# ArtNet_LED_Strip_Controller.net
KiCad netlist of a schematic drawn in EAGLE
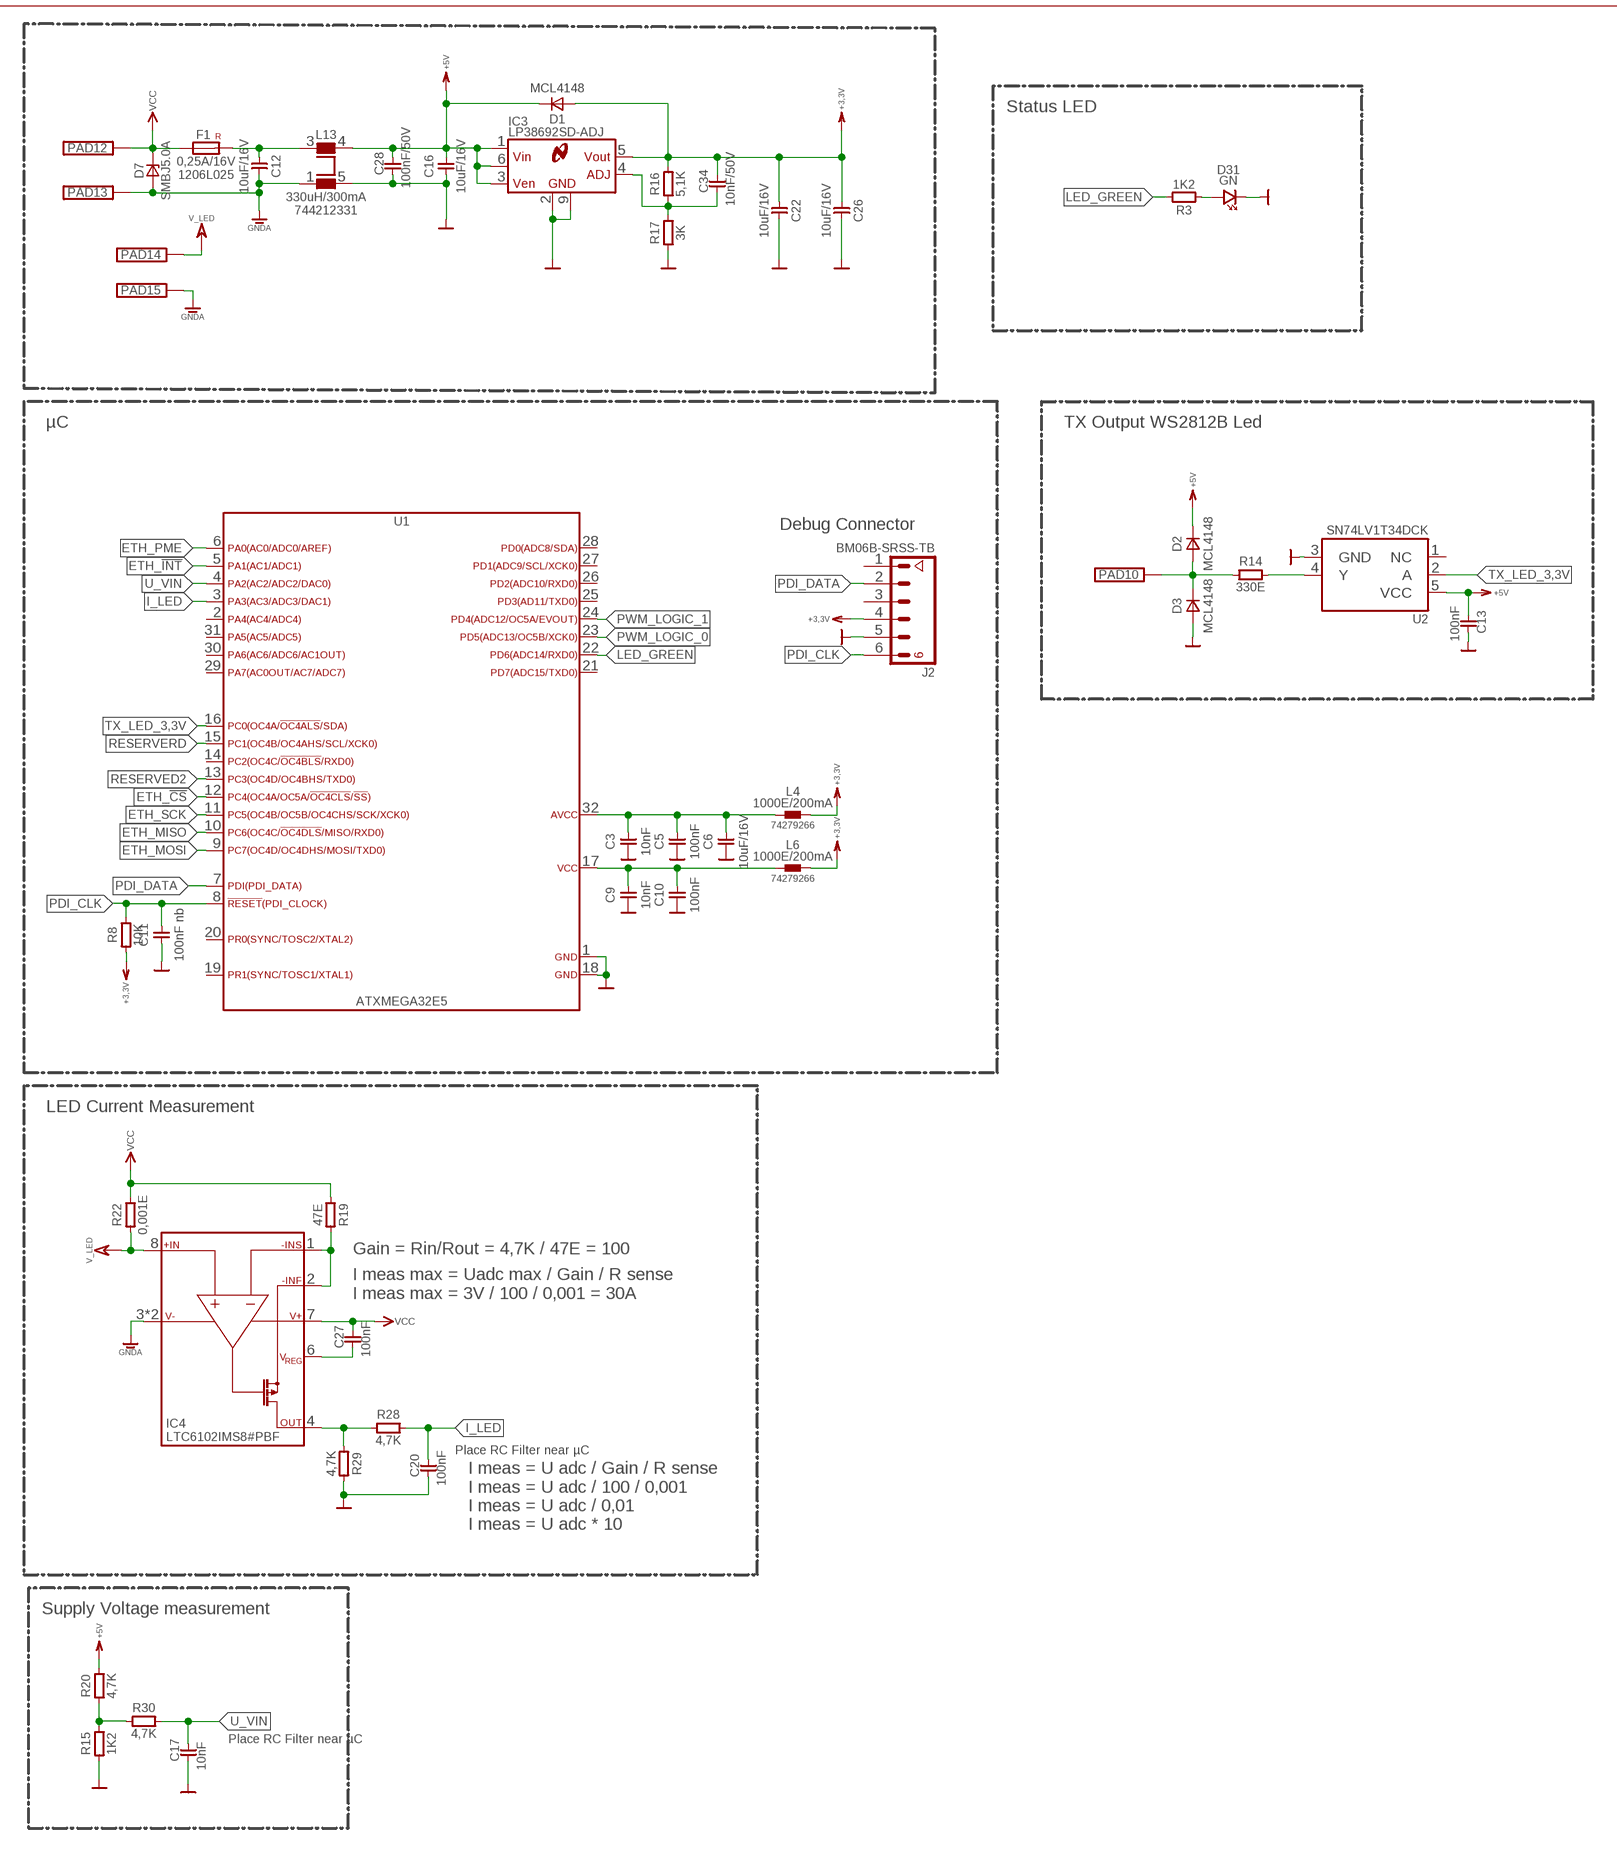
[diagram p0: schematic, sheet 1, part 1 of 2]
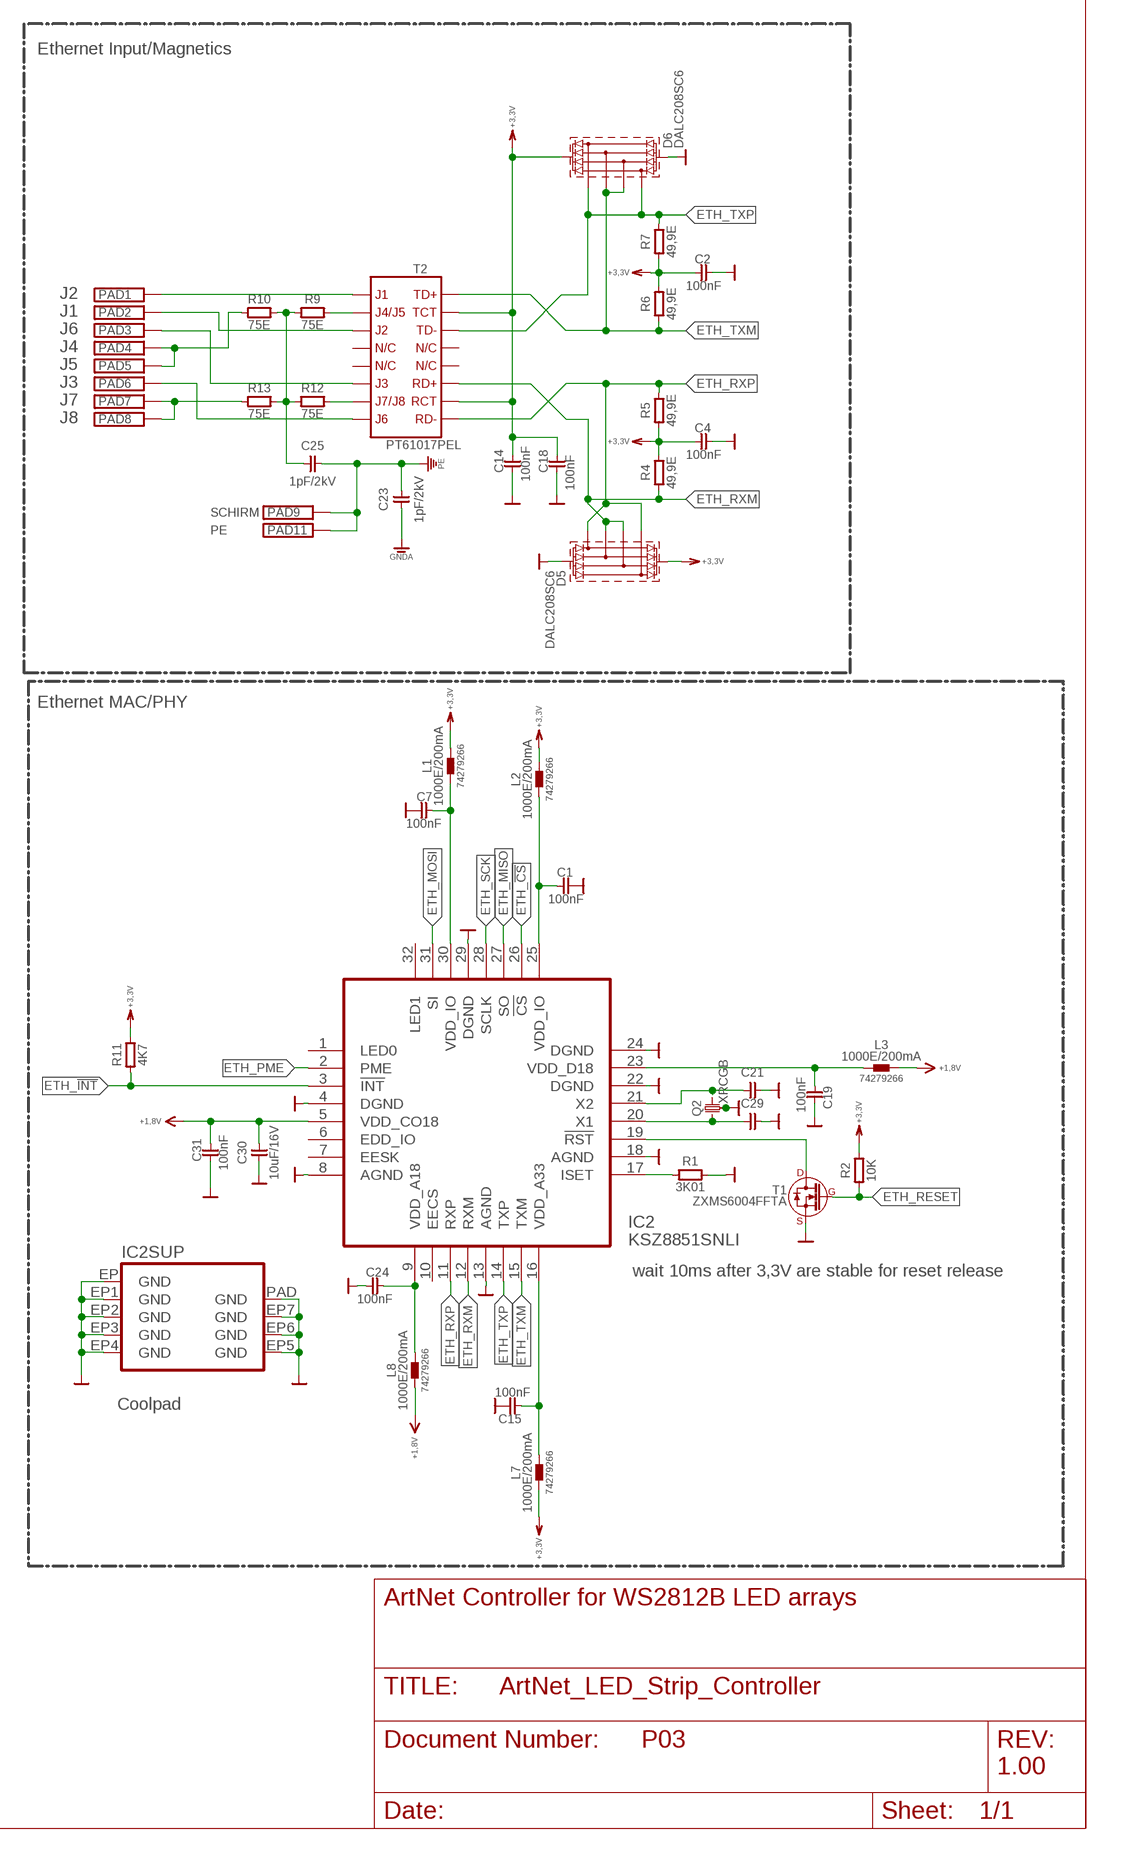
[diagram p1: schematic, sheet 1, part 2 of 2]

(export (version "E")
  (design (tool "Eeschema 10.0.6"))
  (components
    (comp (ref "C1")
      (value "100nF")
      (footprint "eagle-import:0603@1")
      (libsource (lib "eagle-import") (part "C-0603"))
    )
    (comp (ref "C2")
      (value "100nF")
      (footprint "eagle-import:0603@1")
      (libsource (lib "eagle-import") (part "C-0603"))
    )
    (comp (ref "C3")
      (value "10nF")
      (footprint "eagle-import:0603@1")
      (libsource (lib "eagle-import") (part "C-0603"))
    )
    (comp (ref "C4")
      (value "100nF")
      (footprint "eagle-import:0603@1")
      (libsource (lib "eagle-import") (part "C-0603"))
    )
    (comp (ref "C5")
      (value "100nF")
      (footprint "eagle-import:0603@1")
      (libsource (lib "eagle-import") (part "C-0603"))
    )
    (comp (ref "C6")
      (value "10uF/16V")
      (footprint "eagle-import:0805")
      (libsource (lib "eagle-import") (part "C-0805"))
    )
    (comp (ref "C7")
      (value "100nF")
      (footprint "eagle-import:0603@1")
      (libsource (lib "eagle-import") (part "C-0603"))
    )
    (comp (ref "C9")
      (value "10nF")
      (footprint "eagle-import:0603@1")
      (libsource (lib "eagle-import") (part "C-0603"))
    )
    (comp (ref "C10")
      (value "100nF")
      (footprint "eagle-import:0603@1")
      (libsource (lib "eagle-import") (part "C-0603"))
    )
    (comp (ref "C11")
      (value "100nF nb")
      (footprint "eagle-import:0603@1")
      (libsource (lib "eagle-import") (part "C-0603"))
    )
    (comp (ref "C12")
      (value "10uF/16V")
      (footprint "eagle-import:0805")
      (libsource (lib "eagle-import") (part "C-0805"))
    )
    (comp (ref "C13")
      (value "100nF")
      (footprint "eagle-import:0603@1")
      (libsource (lib "eagle-import") (part "C-0603"))
    )
    (comp (ref "C14")
      (value "100nF")
      (footprint "eagle-import:0603@1")
      (libsource (lib "eagle-import") (part "C-0603"))
    )
    (comp (ref "C15")
      (value "100nF")
      (footprint "eagle-import:0603@1")
      (libsource (lib "eagle-import") (part "C-0603"))
    )
    (comp (ref "C16")
      (value "10uF/16V")
      (footprint "eagle-import:0805")
      (libsource (lib "eagle-import") (part "C-0805"))
    )
    (comp (ref "C17")
      (value "10nF")
      (footprint "eagle-import:0603@1")
      (libsource (lib "eagle-import") (part "C-0603"))
    )
    (comp (ref "C18")
      (value "100nF")
      (footprint "eagle-import:0603@1")
      (libsource (lib "eagle-import") (part "C-0603"))
    )
    (comp (ref "C19")
      (value "100nF")
      (footprint "eagle-import:0603@1")
      (libsource (lib "eagle-import") (part "C-0603"))
    )
    (comp (ref "C20")
      (value "100nF")
      (footprint "eagle-import:0603@1")
      (libsource (lib "eagle-import") (part "C-0603"))
    )
    (comp (ref "C21")
      (value "C-0603")
      (footprint "eagle-import:0603@1")
      (libsource (lib "eagle-import") (part "C-0603"))
    )
    (comp (ref "C22")
      (value "10uF/16V")
      (footprint "eagle-import:0805")
      (libsource (lib "eagle-import") (part "C-0805"))
    )
    (comp (ref "C23")
      (value "1pF/2kV")
      (footprint "eagle-import:1206@1")
      (libsource (lib "eagle-import") (part "C-1206"))
    )
    (comp (ref "C24")
      (value "100nF")
      (footprint "eagle-import:0603@1")
      (libsource (lib "eagle-import") (part "C-0603"))
    )
    (comp (ref "C25")
      (value "1pF/2kV")
      (footprint "eagle-import:1206@1")
      (libsource (lib "eagle-import") (part "C-1206"))
    )
    (comp (ref "C26")
      (value "10uF/16V")
      (footprint "eagle-import:0805")
      (libsource (lib "eagle-import") (part "C-0805"))
    )
    (comp (ref "C27")
      (value "100nF")
      (footprint "eagle-import:0603@1")
      (libsource (lib "eagle-import") (part "C-0603"))
    )
    (comp (ref "C28")
      (value "100nF/50V")
      (footprint "eagle-import:0603@1")
      (libsource (lib "eagle-import") (part "C-0603"))
    )
    (comp (ref "C29")
      (value "C-0603")
      (footprint "eagle-import:0603@1")
      (libsource (lib "eagle-import") (part "C-0603"))
    )
    (comp (ref "C30")
      (value "10uF/16V")
      (footprint "eagle-import:0805")
      (libsource (lib "eagle-import") (part "C-0805"))
    )
    (comp (ref "C31")
      (value "100nF")
      (footprint "eagle-import:0603@1")
      (libsource (lib "eagle-import") (part "C-0603"))
    )
    (comp (ref "C34")
      (value "10nF/50V")
      (footprint "eagle-import:0603@1")
      (libsource (lib "eagle-import") (part "C-0603"))
    )
    (comp (ref "D1")
      (value "MCL4148")
      (footprint "eagle-import:MICROMELF")
      (libsource (lib "eagle-import") (part "?4148MCL"))
    )
    (comp (ref "D2")
      (value "MCL4148")
      (footprint "eagle-import:MICROMELF")
      (libsource (lib "eagle-import") (part "?4148MCL"))
    )
    (comp (ref "D3")
      (value "MCL4148")
      (footprint "eagle-import:MICROMELF")
      (libsource (lib "eagle-import") (part "?4148MCL"))
    )
    (comp (ref "D5")
      (value "DALC208SC6")
      (footprint "eagle-import:SOT23-6L")
      (libsource (lib "eagle-import") (part "DALC208SC6"))
    )
    (comp (ref "D6")
      (value "DALC208SC6")
      (footprint "eagle-import:SOT23-6L")
      (libsource (lib "eagle-import") (part "DALC208SC6"))
    )
    (comp (ref "D7")
      (value "SMBJ5.0A")
      (footprint "eagle-import:DO-214AA")
      (libsource (lib "eagle-import") (part "SMBJA5.0"))
    )
    (comp (ref "D31")
      (value "GN")
      (footprint "eagle-import:0603")
      (libsource (lib "eagle-import") (part "LL296A"))
    )
    (comp (ref "F1")
      (value "0,25A/16V")
      (footprint "eagle-import:1206L")
      (fields (field (name "MPN") "1206L025"))
      (libsource (lib "eagle-import") (part "1206L025"))
    )
    (comp (ref "IC2")
      (value "KSZ8851SNLI")
      (footprint "eagle-import:QFN32_5X5")
      (libsource (lib "eagle-import") (part "IC_KSZ8851SNL"))
    )
    (comp (ref "IC3")
      (value "LP38692SD-ADJ")
      (footprint "eagle-import:LLP-6")
      (libsource (lib "eagle-import") (part "LP38692?-ADJSD"))
    )
    (comp (ref "IC4")
      (value "LTC6102IMS8#PBF")
      (footprint "eagle-import:MS8")
      (libsource (lib "eagle-import") (part "LTC6102?#PBFMS8I"))
    )
    (comp (ref "J2")
      (value "BM06B-SRSS-TB")
      (footprint "eagle-import:BM06B-SRSS-TB")
      (libsource (lib "eagle-import") (part "?M06B-SRSS-TBB"))
    )
    (comp (ref "L1")
      (value "1000E/200mA")
      (footprint "eagle-import:0603")
      (fields (field (name "MPN") "74279266"))
      (libsource (lib "eagle-import") (part "WE-CBF-0603-1000E/200MA"))
    )
    (comp (ref "L2")
      (value "1000E/200mA")
      (footprint "eagle-import:0603")
      (fields (field (name "MPN") "74279266"))
      (libsource (lib "eagle-import") (part "WE-CBF-0603-1000E/200MA"))
    )
    (comp (ref "L3")
      (value "1000E/200mA")
      (footprint "eagle-import:0603")
      (fields (field (name "MPN") "74279266"))
      (libsource (lib "eagle-import") (part "WE-CBF-0603-1000E/200MA"))
    )
    (comp (ref "L4")
      (value "1000E/200mA")
      (footprint "eagle-import:0603")
      (fields (field (name "MPN") "74279266"))
      (libsource (lib "eagle-import") (part "WE-CBF-0603-1000E/200MA"))
    )
    (comp (ref "L6")
      (value "1000E/200mA")
      (footprint "eagle-import:0603")
      (fields (field (name "MPN") "74279266"))
      (libsource (lib "eagle-import") (part "WE-CBF-0603-1000E/200MA"))
    )
    (comp (ref "L7")
      (value "1000E/200mA")
      (footprint "eagle-import:0603")
      (fields (field (name "MPN") "74279266"))
      (libsource (lib "eagle-import") (part "WE-CBF-0603-1000E/200MA"))
    )
    (comp (ref "L8")
      (value "1000E/200mA")
      (footprint "eagle-import:0603")
      (fields (field (name "MPN") "74279266"))
      (libsource (lib "eagle-import") (part "WE-CBF-0603-1000E/200MA"))
    )
    (comp (ref "L13")
      (value "330uH/300mA")
      (footprint "eagle-import:WE-SL1")
      (fields (field (name "MPN") "744212331"))
      (libsource (lib "eagle-import") (part "WE-SL1-330UH/300MA"))
    )
    (comp (ref "PAD1")
      (value "PADS-2X1.5")
      (footprint "eagle-import:PAD_2MMX1,4MM")
      (libsource (lib "eagle-import") (part "PADS-2X1.5"))
    )
    (comp (ref "PAD2")
      (value "PADS-2X1.5")
      (footprint "eagle-import:PAD_2MMX1,4MM")
      (libsource (lib "eagle-import") (part "PADS-2X1.5"))
    )
    (comp (ref "PAD3")
      (value "PADS-2X1.5")
      (footprint "eagle-import:PAD_2MMX1,4MM")
      (libsource (lib "eagle-import") (part "PADS-2X1.5"))
    )
    (comp (ref "PAD4")
      (value "PADS-2X1.5")
      (footprint "eagle-import:PAD_2MMX1,4MM")
      (libsource (lib "eagle-import") (part "PADS-2X1.5"))
    )
    (comp (ref "PAD5")
      (value "PADS-2X1.5")
      (footprint "eagle-import:PAD_2MMX1,4MM")
      (libsource (lib "eagle-import") (part "PADS-2X1.5"))
    )
    (comp (ref "PAD6")
      (value "PADS-2X1.5")
      (footprint "eagle-import:PAD_2MMX1,4MM")
      (libsource (lib "eagle-import") (part "PADS-2X1.5"))
    )
    (comp (ref "PAD7")
      (value "PADS-2X1.5")
      (footprint "eagle-import:PAD_2MMX1,4MM")
      (libsource (lib "eagle-import") (part "PADS-2X1.5"))
    )
    (comp (ref "PAD8")
      (value "PADS-2X1.5")
      (footprint "eagle-import:PAD_2MMX1,4MM")
      (libsource (lib "eagle-import") (part "PADS-2X1.5"))
    )
    (comp (ref "PAD9")
      (value "PADS-2X1.5")
      (footprint "eagle-import:PAD_2MMX1,4MM")
      (libsource (lib "eagle-import") (part "PADS-2X1.5"))
    )
    (comp (ref "PAD10")
      (value "PADS-2X1.5")
      (footprint "eagle-import:PAD_2MMX1,4MM")
      (libsource (lib "eagle-import") (part "PADS-2X1.5"))
    )
    (comp (ref "PAD11")
      (value "PADS-2X1.5")
      (footprint "eagle-import:PAD_2MMX1,4MM")
      (libsource (lib "eagle-import") (part "PADS-2X1.5"))
    )
    (comp (ref "PAD12")
      (value "PADS-8X5_O_P")
      (footprint "eagle-import:PAD_8MMX5MM_OHNE_PASTE")
      (libsource (lib "eagle-import") (part "PADS-8X5_O_P"))
    )
    (comp (ref "PAD13")
      (value "PADS-8X5_O_P")
      (footprint "eagle-import:PAD_8MMX5MM_OHNE_PASTE")
      (libsource (lib "eagle-import") (part "PADS-8X5_O_P"))
    )
    (comp (ref "PAD14")
      (value "PADS-8X5_O_P")
      (footprint "eagle-import:PAD_8MMX5MM_OHNE_PASTE")
      (libsource (lib "eagle-import") (part "PADS-8X5_O_P"))
    )
    (comp (ref "PAD15")
      (value "PADS-8X5_O_P")
      (footprint "eagle-import:PAD_8MMX5MM_OHNE_PASTE")
      (libsource (lib "eagle-import") (part "PADS-8X5_O_P"))
    )
    (comp (ref "Q2")
      (value "XRCGB")
      (footprint "eagle-import:XRCGB")
      (libsource (lib "eagle-import") (part "XRCGB"))
    )
    (comp (ref "R1")
      (value "3K01")
      (footprint "eagle-import:0603")
      (libsource (lib "eagle-import") (part "R-0603"))
    )
    (comp (ref "R2")
      (value "10K")
      (footprint "eagle-import:0603")
      (libsource (lib "eagle-import") (part "R-0603"))
    )
    (comp (ref "R3")
      (value "1K2")
      (footprint "eagle-import:0603")
      (libsource (lib "eagle-import") (part "R-0603"))
    )
    (comp (ref "R4")
      (value "49,9E")
      (footprint "eagle-import:0603")
      (libsource (lib "eagle-import") (part "R-0603"))
    )
    (comp (ref "R5")
      (value "49,9E")
      (footprint "eagle-import:0603")
      (libsource (lib "eagle-import") (part "R-0603"))
    )
    (comp (ref "R6")
      (value "49,9E")
      (footprint "eagle-import:0603")
      (libsource (lib "eagle-import") (part "R-0603"))
    )
    (comp (ref "R7")
      (value "49,9E")
      (footprint "eagle-import:0603")
      (libsource (lib "eagle-import") (part "R-0603"))
    )
    (comp (ref "R8")
      (value "10K")
      (footprint "eagle-import:0603")
      (libsource (lib "eagle-import") (part "R-0603"))
    )
    (comp (ref "R9")
      (value "75E")
      (footprint "eagle-import:0603")
      (libsource (lib "eagle-import") (part "R-0603"))
    )
    (comp (ref "R10")
      (value "75E")
      (footprint "eagle-import:0603")
      (libsource (lib "eagle-import") (part "R-0603"))
    )
    (comp (ref "R11")
      (value "4K7")
      (footprint "eagle-import:0603")
      (libsource (lib "eagle-import") (part "R-0603"))
    )
    (comp (ref "R12")
      (value "75E")
      (footprint "eagle-import:0603")
      (libsource (lib "eagle-import") (part "R-0603"))
    )
    (comp (ref "R13")
      (value "75E")
      (footprint "eagle-import:0603")
      (libsource (lib "eagle-import") (part "R-0603"))
    )
    (comp (ref "R14")
      (value "330E")
      (footprint "eagle-import:0603")
      (libsource (lib "eagle-import") (part "R-0603"))
    )
    (comp (ref "R15")
      (value "1K2")
      (footprint "eagle-import:0603")
      (libsource (lib "eagle-import") (part "R-0603"))
    )
    (comp (ref "R16")
      (value "5,1K")
      (footprint "eagle-import:0603")
      (libsource (lib "eagle-import") (part "R-0603"))
    )
    (comp (ref "R17")
      (value "3K")
      (footprint "eagle-import:0603")
      (libsource (lib "eagle-import") (part "R-0603"))
    )
    (comp (ref "R19")
      (value "47E")
      (footprint "eagle-import:0603")
      (libsource (lib "eagle-import") (part "R-0603"))
    )
    (comp (ref "R20")
      (value "4,7K")
      (footprint "eagle-import:0603")
      (libsource (lib "eagle-import") (part "R-0603"))
    )
    (comp (ref "R22")
      (value "0,001E")
      (footprint "eagle-import:WSL2512_2")
      (libsource (lib "eagle-import") (part "R-WSL2512_2"))
    )
    (comp (ref "R28")
      (value "4,7K")
      (footprint "eagle-import:0603")
      (libsource (lib "eagle-import") (part "R-0603"))
    )
    (comp (ref "R29")
      (value "4,7K")
      (footprint "eagle-import:0603")
      (libsource (lib "eagle-import") (part "R-0603"))
    )
    (comp (ref "R30")
      (value "4,7K")
      (footprint "eagle-import:0603")
      (libsource (lib "eagle-import") (part "R-0603"))
    )
    (comp (ref "T1")
      (value "ZXMS6004FFTA")
      (footprint "eagle-import:SOT-23")
      (libsource (lib "eagle-import") (part "ZXMS6004?TAFF"))
    )
    (comp (ref "T2")
      (value "PT61017PEL")
      (footprint "eagle-import:PT61017")
      (libsource (lib "eagle-import") (part "PT61017PEL"))
    )
    (comp (ref "U1")
      (value "ATXMEGA32E5")
      (footprint "eagle-import:32_UQFN")
      (libsource (lib "eagle-import") (part "ATXMEGA32E5"))
    )
    (comp (ref "U2")
      (value "SN74LV1T34DCK")
      (footprint "eagle-import:DCK0005A_N")
      (fields (field (name "MANUFACTURER") "Texas Instruments"))
      (libsource (lib "eagle-import") (part "SN74LV1T34DCKR"))
    )
  )
  (nets
    (net (code "1") (name "+1,8V") (class "Default")
      (node (ref "C30") (pin "2") (pinfunction "2_2") (pintype "passive"))
      (node (ref "C31") (pin "2") (pinfunction "2_2") (pintype "passive"))
      (node (ref "IC2") (pin "5") (pinfunction "VDD_CO18_5") (pintype "bidirectional"))
      (node (ref "L3") (pin "2") (pinfunction "2_2") (pintype "passive"))
      (node (ref "L8") (pin "1") (pinfunction "1_1") (pintype "passive"))
    )
    (net (code "2") (name "+3,3V") (class "Default")
      (node (ref "C14") (pin "2") (pinfunction "2_2") (pintype "passive"))
      (node (ref "C18") (pin "2") (pinfunction "2_2") (pintype "passive"))
      (node (ref "C2") (pin "1") (pinfunction "1_1") (pintype "passive"))
      (node (ref "C22") (pin "1") (pinfunction "1_1") (pintype "passive"))
      (node (ref "C26") (pin "1") (pinfunction "1_1") (pintype "passive"))
      (node (ref "C34") (pin "2") (pinfunction "2_2") (pintype "passive"))
      (node (ref "C4") (pin "1") (pinfunction "1_1") (pintype "passive"))
      (node (ref "D1") (pin "A") (pinfunction "A_A") (pintype "passive"))
      (node (ref "D5") (pin "2") (pinfunction "REF2_2") (pintype "passive"))
      (node (ref "D6") (pin "2") (pinfunction "REF2_2") (pintype "passive"))
      (node (ref "IC3") (pin "5") (pinfunction "VOUT_5") (pintype "power_in"))
      (node (ref "J2") (pin "4") (pinfunction "4_4") (pintype "passive"))
      (node (ref "L1") (pin "2") (pinfunction "2_2") (pintype "passive"))
      (node (ref "L2") (pin "2") (pinfunction "2_2") (pintype "passive"))
      (node (ref "L4") (pin "2") (pinfunction "2_2") (pintype "passive"))
      (node (ref "L6") (pin "2") (pinfunction "2_2") (pintype "passive"))
      (node (ref "L7") (pin "1") (pinfunction "1_1") (pintype "passive"))
      (node (ref "R11") (pin "2") (pinfunction "2_2") (pintype "passive"))
      (node (ref "R16") (pin "2") (pinfunction "2_2") (pintype "passive"))
      (node (ref "R2") (pin "2") (pinfunction "2_2") (pintype "passive"))
      (node (ref "R4") (pin "2") (pinfunction "2_2") (pintype "passive"))
      (node (ref "R5") (pin "1") (pinfunction "1_1") (pintype "passive"))
      (node (ref "R6") (pin "2") (pinfunction "2_2") (pintype "passive"))
      (node (ref "R7") (pin "1") (pinfunction "1_1") (pintype "passive"))
      (node (ref "R8") (pin "1") (pinfunction "1_1") (pintype "passive"))
      (node (ref "T2") (pin "2") (pinfunction "P$2_2") (pintype "bidirectional"))
      (node (ref "T2") (pin "7") (pinfunction "P$7_7") (pintype "bidirectional"))
    )
    (net (code "3") (name "+5V") (class "Default")
      (node (ref "C13") (pin "1") (pinfunction "1_1") (pintype "passive"))
      (node (ref "C16") (pin "2") (pinfunction "2_2") (pintype "passive"))
      (node (ref "C28") (pin "2") (pinfunction "2_2") (pintype "passive"))
      (node (ref "D1") (pin "K") (pinfunction "K_K") (pintype "passive"))
      (node (ref "D2") (pin "K") (pinfunction "K_K") (pintype "passive"))
      (node (ref "IC3") (pin "1") (pinfunction "VIN_1") (pintype "power_in"))
      (node (ref "IC3") (pin "3") (pinfunction "VEN_3") (pintype "input"))
      (node (ref "IC3") (pin "6") (pinfunction "VIN1_6") (pintype "power_in"))
      (node (ref "L13") (pin "4") (pinfunction "3_4") (pintype "passive"))
      (node (ref "R20") (pin "2") (pinfunction "2_2") (pintype "passive"))
      (node (ref "U2") (pin "5") (pinfunction "VCC_5") (pintype "power_in"))
    )
    (net (code "4") (name "/ETH_~{CS}") (class "Default")
      (node (ref "IC2") (pin "26") (pinfunction "~{CS}_26") (pintype "bidirectional"))
      (node (ref "U1") (pin "12") (pinfunction "PC4_12") (pintype "bidirectional"))
    )
    (net (code "5") (name "/ETH_~{INT}") (class "Default")
      (node (ref "IC2") (pin "3") (pinfunction "~{INT}_3") (pintype "bidirectional"))
      (node (ref "R11") (pin "1") (pinfunction "1_1") (pintype "passive"))
      (node (ref "U1") (pin "5") (pinfunction "PA1_5") (pintype "bidirectional"))
    )
    (net (code "6") (name "ETH_MISO") (class "Default")
      (node (ref "IC2") (pin "27") (pinfunction "SO_27") (pintype "bidirectional"))
      (node (ref "U1") (pin "10") (pinfunction "PC6_10") (pintype "bidirectional"))
    )
    (net (code "7") (name "ETH_MOSI") (class "Default")
      (node (ref "IC2") (pin "31") (pinfunction "SI_31") (pintype "bidirectional"))
      (node (ref "U1") (pin "9") (pinfunction "PC7_9") (pintype "bidirectional"))
    )
    (net (code "8") (name "ETH_PME") (class "Default")
      (node (ref "IC2") (pin "2") (pinfunction "PME_2") (pintype "bidirectional"))
      (node (ref "U1") (pin "6") (pinfunction "PA0_6") (pintype "bidirectional"))
    )
    (net (code "9") (name "ETH_RESET") (class "Default")
      (node (ref "R2") (pin "1") (pinfunction "1_1") (pintype "passive"))
      (node (ref "T1") (pin "1") (pinfunction "G_1") (pintype "passive"))
    )
    (net (code "10") (name "ETH_RXM") (class "Default")
      (node (ref "D5") (pin "3") (pinfunction "I/O2_3") (pintype "passive"))
      (node (ref "D5") (pin "4") (pinfunction "I/O3_4") (pintype "passive"))
      (node (ref "IC2") (pin "12") (pinfunction "RXM_12") (pintype "bidirectional"))
      (node (ref "R4") (pin "1") (pinfunction "1_1") (pintype "passive"))
      (node (ref "T2") (pin "6") (pinfunction "P$6_6") (pintype "bidirectional"))
    )
    (net (code "11") (name "ETH_RXP") (class "Default")
      (node (ref "D5") (pin "1") (pinfunction "I/O1_1") (pintype "passive"))
      (node (ref "D5") (pin "6") (pinfunction "I/O4_6") (pintype "passive"))
      (node (ref "IC2") (pin "11") (pinfunction "RXP_11") (pintype "bidirectional"))
      (node (ref "R5") (pin "2") (pinfunction "2_2") (pintype "passive"))
      (node (ref "T2") (pin "8") (pinfunction "P$8_8") (pintype "bidirectional"))
    )
    (net (code "12") (name "ETH_SCK") (class "Default")
      (node (ref "IC2") (pin "28") (pinfunction "SCLK_28") (pintype "bidirectional"))
      (node (ref "U1") (pin "11") (pinfunction "PC5_11") (pintype "bidirectional"))
    )
    (net (code "13") (name "ETH_TXM") (class "Default")
      (node (ref "D6") (pin "3") (pinfunction "I/O2_3") (pintype "passive"))
      (node (ref "D6") (pin "4") (pinfunction "I/O3_4") (pintype "passive"))
      (node (ref "IC2") (pin "15") (pinfunction "TXM_15") (pintype "bidirectional"))
      (node (ref "R6") (pin "1") (pinfunction "1_1") (pintype "passive"))
      (node (ref "T2") (pin "1") (pinfunction "P$1_1") (pintype "bidirectional"))
    )
    (net (code "14") (name "ETH_TXP") (class "Default")
      (node (ref "D6") (pin "1") (pinfunction "I/O1_1") (pintype "passive"))
      (node (ref "D6") (pin "6") (pinfunction "I/O4_6") (pintype "passive"))
      (node (ref "IC2") (pin "14") (pinfunction "TXP_14") (pintype "bidirectional"))
      (node (ref "R7") (pin "2") (pinfunction "2_2") (pintype "passive"))
      (node (ref "T2") (pin "3") (pinfunction "P$3_3") (pintype "bidirectional"))
    )
    (net (code "15") (name "GND") (class "Default")
      (node (ref "C1") (pin "2") (pinfunction "2_2") (pintype "passive"))
      (node (ref "C10") (pin "1") (pinfunction "1_1") (pintype "passive"))
      (node (ref "C11") (pin "1") (pinfunction "1_1") (pintype "passive"))
      (node (ref "C13") (pin "2") (pinfunction "2_2") (pintype "passive"))
      (node (ref "C14") (pin "1") (pinfunction "1_1") (pintype "passive"))
      (node (ref "C15") (pin "2") (pinfunction "2_2") (pintype "passive"))
      (node (ref "C16") (pin "1") (pinfunction "1_1") (pintype "passive"))
      (node (ref "C17") (pin "1") (pinfunction "1_1") (pintype "passive"))
      (node (ref "C18") (pin "1") (pinfunction "1_1") (pintype "passive"))
      (node (ref "C19") (pin "2") (pinfunction "2_2") (pintype "passive"))
      (node (ref "C2") (pin "2") (pinfunction "2_2") (pintype "passive"))
      (node (ref "C20") (pin "1") (pinfunction "1_1") (pintype "passive"))
      (node (ref "C21") (pin "2") (pinfunction "2_2") (pintype "passive"))
      (node (ref "C22") (pin "2") (pinfunction "2_2") (pintype "passive"))
      (node (ref "C24") (pin "1") (pinfunction "1_1") (pintype "passive"))
      (node (ref "C26") (pin "2") (pinfunction "2_2") (pintype "passive"))
      (node (ref "C28") (pin "1") (pinfunction "1_1") (pintype "passive"))
      (node (ref "C29") (pin "2") (pinfunction "2_2") (pintype "passive"))
      (node (ref "C3") (pin "1") (pinfunction "1_1") (pintype "passive"))
      (node (ref "C30") (pin "1") (pinfunction "1_1") (pintype "passive"))
      (node (ref "C31") (pin "1") (pinfunction "1_1") (pintype "passive"))
      (node (ref "C4") (pin "2") (pinfunction "2_2") (pintype "passive"))
      (node (ref "C5") (pin "1") (pinfunction "1_1") (pintype "passive"))
      (node (ref "C6") (pin "1") (pinfunction "1_1") (pintype "passive"))
      (node (ref "C7") (pin "2") (pinfunction "2_2") (pintype "passive"))
      (node (ref "C9") (pin "1") (pinfunction "1_1") (pintype "passive"))
      (node (ref "D3") (pin "A") (pinfunction "A_A") (pintype "passive"))
      (node (ref "D31") (pin "K") (pinfunction "K_K") (pintype "passive"))
      (node (ref "D5") (pin "5") (pinfunction "REF1_5") (pintype "passive"))
      (node (ref "D6") (pin "5") (pinfunction "REF1_5") (pintype "passive"))
      (node (ref "IC2") (pin "13") (pinfunction "AGND_13") (pintype "bidirectional"))
      (node (ref "IC2") (pin "18") (pinfunction "AGND_18") (pintype "power_in"))
      (node (ref "IC2") (pin "22") (pinfunction "DGND_22") (pintype "bidirectional"))
      (node (ref "IC2") (pin "24") (pinfunction "DGND_24") (pintype "bidirectional"))
      (node (ref "IC2") (pin "29") (pinfunction "DGND_29") (pintype "bidirectional"))
      (node (ref "IC2") (pin "4") (pinfunction "DGND_4") (pintype "power_in"))
      (node (ref "IC2") (pin "8") (pinfunction "AGND_8") (pintype "bidirectional"))
      (node (ref "IC2") (pin "EP") (pinfunction "GND_EP") (pintype "power_in"))
      (node (ref "IC2") (pin "EP1") (pinfunction "GND_EP1") (pintype "power_in"))
      (node (ref "IC2") (pin "EP2") (pinfunction "GND_EP2") (pintype "power_in"))
      (node (ref "IC2") (pin "EP3") (pinfunction "GND_EP3") (pintype "power_in"))
      (node (ref "IC2") (pin "EP4") (pinfunction "GND_EP4") (pintype "power_in"))
      (node (ref "IC2") (pin "EP5") (pinfunction "GND_EP5") (pintype "power_in"))
      (node (ref "IC2") (pin "EP6") (pinfunction "GND_EP6") (pintype "power_in"))
      (node (ref "IC2") (pin "EP7") (pinfunction "GND_EP7") (pintype "power_in"))
      (node (ref "IC2") (pin "PAD") (pinfunction "GND_PAD") (pintype "power_in"))
      (node (ref "IC3") (pin "2") (pinfunction "GND_2") (pintype "power_in"))
      (node (ref "IC3") (pin "9") (pinfunction "GND1_9") (pintype "power_in"))
      (node (ref "J2") (pin "5") (pinfunction "5_5") (pintype "passive"))
      (node (ref "L13") (pin "5") (pinfunction "2_5") (pintype "passive"))
      (node (ref "Q2") (pin "3") (pinfunction "P$3_3") (pintype "bidirectional"))
      (node (ref "Q2") (pin "4") (pinfunction "P$4_4") (pintype "bidirectional"))
      (node (ref "R1") (pin "2") (pinfunction "2_2") (pintype "passive"))
      (node (ref "R15") (pin "1") (pinfunction "1_1") (pintype "passive"))
      (node (ref "R17") (pin "1") (pinfunction "1_1") (pintype "passive"))
      (node (ref "R29") (pin "2") (pinfunction "2_2") (pintype "passive"))
      (node (ref "T1") (pin "2") (pinfunction "S_2") (pintype "passive"))
      (node (ref "U1") (pin "1") (pinfunction "GND_1") (pintype "power_in"))
      (node (ref "U1") (pin "18") (pinfunction "GND_18") (pintype "power_in"))
      (node (ref "U2") (pin "3") (pinfunction "GND_3") (pintype "power_in"))
    )
    (net (code "16") (name "GNDA") (class "Default")
      (node (ref "C12") (pin "2") (pinfunction "2_2") (pintype "passive"))
      (node (ref "C23") (pin "1") (pinfunction "1_1") (pintype "passive"))
      (node (ref "D7") (pin "A") (pinfunction "A_A") (pintype "passive"))
      (node (ref "IC4") (pin "3") (pinfunction "V-_3") (pintype "power_in"))
      (node (ref "IC4") (pin "5") (pinfunction "V-_5") (pintype "power_in"))
      (node (ref "L13") (pin "1") (pinfunction "1_1") (pintype "passive"))
      (node (ref "PAD13") (pin "P$1") (pinfunction "1_P$1") (pintype "bidirectional"))
      (node (ref "PAD15") (pin "P$1") (pinfunction "1_P$1") (pintype "bidirectional"))
    )
    (net (code "17") (name "I_LED") (class "Default")
      (node (ref "C20") (pin "2") (pinfunction "2_2") (pintype "passive"))
      (node (ref "R28") (pin "2") (pinfunction "2_2") (pintype "passive"))
      (node (ref "U1") (pin "3") (pinfunction "PA3_3") (pintype "bidirectional"))
    )
    (net (code "18") (name "LED_GREEN") (class "Default")
      (node (ref "R3") (pin "2") (pinfunction "2_2") (pintype "passive"))
      (node (ref "U1") (pin "22") (pinfunction "PD6_22") (pintype "bidirectional"))
    )
    (net (code "19") (name "Net-(C1-Pad1)") (class "Default")
      (node (ref "C1") (pin "1") (pinfunction "1_1") (pintype "passive"))
      (node (ref "IC2") (pin "25") (pinfunction "VDD_IO_25") (pintype "bidirectional"))
      (node (ref "L2") (pin "1") (pinfunction "1_1") (pintype "passive"))
    )
    (net (code "20") (name "Net-(C7-Pad1)") (class "Default")
      (node (ref "C7") (pin "1") (pinfunction "1_1") (pintype "passive"))
      (node (ref "IC2") (pin "30") (pinfunction "VDD_IO_30") (pintype "bidirectional"))
      (node (ref "L1") (pin "1") (pinfunction "1_1") (pintype "passive"))
    )
    (net (code "21") (name "Net-(C25-Pad1)") (class "Default")
      (node (ref "C25") (pin "1") (pinfunction "1_1") (pintype "passive"))
      (node (ref "R10") (pin "2") (pinfunction "2_2") (pintype "passive"))
      (node (ref "R12") (pin "1") (pinfunction "1_1") (pintype "passive"))
      (node (ref "R13") (pin "2") (pinfunction "2_2") (pintype "passive"))
      (node (ref "R9") (pin "1") (pinfunction "1_1") (pintype "passive"))
    )
    (net (code "22") (name "Net-(D2-PadA)") (class "Default")
      (node (ref "D2") (pin "A") (pinfunction "A_A") (pintype "passive"))
      (node (ref "D3") (pin "K") (pinfunction "K_K") (pintype "passive"))
      (node (ref "PAD10") (pin "1") (pinfunction "1_1") (pintype "bidirectional"))
      (node (ref "R14") (pin "1") (pinfunction "1_1") (pintype "passive"))
    )
    (net (code "23") (name "Net-(D31-PadA)") (class "Default")
      (node (ref "D31") (pin "A") (pinfunction "A_A") (pintype "passive"))
      (node (ref "R3") (pin "1") (pinfunction "1_1") (pintype "passive"))
    )
    (net (code "24") (name "Net-(IC2A-ISET)") (class "Default")
      (node (ref "IC2") (pin "17") (pinfunction "ISET_17") (pintype "bidirectional"))
      (node (ref "R1") (pin "1") (pinfunction "1_1") (pintype "passive"))
    )
    (net (code "25") (name "Net-(IC2A-VDD_A18)") (class "Default")
      (node (ref "C24") (pin "2") (pinfunction "2_2") (pintype "passive"))
      (node (ref "IC2") (pin "9") (pinfunction "VDD_A18_9") (pintype "bidirectional"))
      (node (ref "L8") (pin "2") (pinfunction "2_2") (pintype "passive"))
    )
    (net (code "26") (name "Net-(IC2A-VDD_A33)") (class "Default")
      (node (ref "C15") (pin "1") (pinfunction "1_1") (pintype "passive"))
      (node (ref "IC2") (pin "16") (pinfunction "VDD_A33_16") (pintype "bidirectional"))
      (node (ref "L7") (pin "2") (pinfunction "2_2") (pintype "passive"))
    )
    (net (code "27") (name "Net-(IC2A-VDD_D18)") (class "Default")
      (node (ref "C19") (pin "1") (pinfunction "1_1") (pintype "passive"))
      (node (ref "IC2") (pin "23") (pinfunction "VDD_D18_23") (pintype "power_in"))
      (node (ref "L3") (pin "1") (pinfunction "1_1") (pintype "passive"))
    )
    (net (code "28") (name "Net-(IC2A-X1)") (class "Default")
      (node (ref "C29") (pin "1") (pinfunction "1_1") (pintype "passive"))
      (node (ref "IC2") (pin "20") (pinfunction "X1_20") (pintype "bidirectional"))
      (node (ref "Q2") (pin "1") (pinfunction "P$1_1") (pintype "passive"))
    )
    (net (code "29") (name "Net-(IC2A-X2)") (class "Default")
      (node (ref "C21") (pin "1") (pinfunction "1_1") (pintype "passive"))
      (node (ref "IC2") (pin "21") (pinfunction "X2_21") (pintype "bidirectional"))
      (node (ref "Q2") (pin "2") (pinfunction "P$2_2") (pintype "passive"))
    )
    (net (code "30") (name "Net-(IC2A-~{RST})") (class "Default")
      (node (ref "IC2") (pin "19") (pinfunction "~{RST}_19") (pintype "bidirectional"))
      (node (ref "T1") (pin "3") (pinfunction "D_3") (pintype "passive"))
    )
    (net (code "31") (name "Net-(IC3-ADJ)") (class "Default")
      (node (ref "C34") (pin "1") (pinfunction "1_1") (pintype "passive"))
      (node (ref "IC3") (pin "4") (pinfunction "ADJ_4") (pintype "input"))
      (node (ref "R16") (pin "1") (pinfunction "1_1") (pintype "passive"))
      (node (ref "R17") (pin "2") (pinfunction "2_2") (pintype "passive"))
    )
    (net (code "32") (name "Net-(IC4--INF)") (class "Default")
      (node (ref "IC4") (pin "1") (pinfunction "-INS_1") (pintype "input"))
      (node (ref "IC4") (pin "2") (pinfunction "-INF_2") (pintype "input"))
      (node (ref "R19") (pin "2") (pinfunction "2_2") (pintype "passive"))
    )
    (net (code "33") (name "Net-(IC4-OUT)") (class "Default")
      (node (ref "IC4") (pin "4") (pinfunction "OUT_4") (pintype "open_collector"))
      (node (ref "R28") (pin "1") (pinfunction "1_1") (pintype "passive"))
      (node (ref "R29") (pin "1") (pinfunction "1_1") (pintype "passive"))
    )
    (net (code "34") (name "Net-(IC4-VREG)") (class "Default")
      (node (ref "C27") (pin "1") (pinfunction "1_1") (pintype "passive"))
      (node (ref "IC4") (pin "6") (pinfunction "VREG_6") (pintype "bidirectional"))
    )
    (net (code "35") (name "Net-(L13-4)") (class "Default")
      (node (ref "C12") (pin "1") (pinfunction "1_1") (pintype "passive"))
      (node (ref "F1") (pin "2") (pinfunction "2_2") (pintype "passive"))
      (node (ref "L13") (pin "3") (pinfunction "4_3") (pintype "passive"))
    )
    (net (code "36") (name "Net-(PAD4-Pad1)") (class "Default")
      (node (ref "PAD4") (pin "1") (pinfunction "1_1") (pintype "bidirectional"))
      (node (ref "PAD5") (pin "1") (pinfunction "1_1") (pintype "bidirectional"))
      (node (ref "R10") (pin "1") (pinfunction "1_1") (pintype "passive"))
    )
    (net (code "37") (name "Net-(PAD7-Pad1)") (class "Default")
      (node (ref "PAD7") (pin "1") (pinfunction "1_1") (pintype "bidirectional"))
      (node (ref "PAD8") (pin "1") (pinfunction "1_1") (pintype "bidirectional"))
      (node (ref "R13") (pin "1") (pinfunction "1_1") (pintype "passive"))
    )
    (net (code "38") (name "Net-(R15-Pad2)") (class "Default")
      (node (ref "R15") (pin "2") (pinfunction "2_2") (pintype "passive"))
      (node (ref "R20") (pin "1") (pinfunction "1_1") (pintype "passive"))
      (node (ref "R30") (pin "1") (pinfunction "1_1") (pintype "passive"))
    )
    (net (code "39") (name "Net-(T2-P$9)") (class "Default")
      (node (ref "PAD6") (pin "1") (pinfunction "1_1") (pintype "bidirectional"))
      (node (ref "T2") (pin "9") (pinfunction "P$9_9") (pintype "bidirectional"))
    )
    (net (code "40") (name "Net-(T2-P$10)") (class "Default")
      (node (ref "R12") (pin "2") (pinfunction "2_2") (pintype "passive"))
      (node (ref "T2") (pin "10") (pinfunction "P$10_10") (pintype "bidirectional"))
    )
    (net (code "41") (name "Net-(T2-P$11)") (class "Default")
      (node (ref "PAD3") (pin "1") (pinfunction "1_1") (pintype "bidirectional"))
      (node (ref "T2") (pin "11") (pinfunction "P$11_11") (pintype "bidirectional"))
    )
    (net (code "42") (name "Net-(T2-P$14)") (class "Default")
      (node (ref "PAD2") (pin "1") (pinfunction "1_1") (pintype "bidirectional"))
      (node (ref "T2") (pin "14") (pinfunction "P$14_14") (pintype "bidirectional"))
    )
    (net (code "43") (name "Net-(T2-P$15)") (class "Default")
      (node (ref "R9") (pin "2") (pinfunction "2_2") (pintype "passive"))
      (node (ref "T2") (pin "15") (pinfunction "P$15_15") (pintype "bidirectional"))
    )
    (net (code "44") (name "Net-(T2-P$16)") (class "Default")
      (node (ref "PAD1") (pin "1") (pinfunction "1_1") (pintype "bidirectional"))
      (node (ref "T2") (pin "16") (pinfunction "P$16_16") (pintype "bidirectional"))
    )
    (net (code "45") (name "Net-(U1-AVCC)") (class "Default")
      (node (ref "C3") (pin "2") (pinfunction "2_2") (pintype "passive"))
      (node (ref "C5") (pin "2") (pinfunction "2_2") (pintype "passive"))
      (node (ref "C6") (pin "2") (pinfunction "2_2") (pintype "passive"))
      (node (ref "L4") (pin "1") (pinfunction "1_1") (pintype "passive"))
      (node (ref "U1") (pin "32") (pinfunction "AVCC_32") (pintype "power_in"))
    )
    (net (code "46") (name "Net-(U1-VCC)") (class "Default")
      (node (ref "C10") (pin "2") (pinfunction "2_2") (pintype "passive"))
      (node (ref "C9") (pin "2") (pinfunction "2_2") (pintype "passive"))
      (node (ref "L6") (pin "1") (pinfunction "1_1") (pintype "passive"))
      (node (ref "U1") (pin "17") (pinfunction "VCC_17") (pintype "power_in"))
    )
    (net (code "47") (name "Net-(U2-Y)") (class "Default")
      (node (ref "R14") (pin "2") (pinfunction "2_2") (pintype "passive"))
      (node (ref "U2") (pin "4") (pinfunction "Y_4") (pintype "bidirectional"))
    )
    (net (code "48") (name "PDI_CLK") (class "Default")
      (node (ref "C11") (pin "2") (pinfunction "2_2") (pintype "passive"))
      (node (ref "J2") (pin "6") (pinfunction "6_6") (pintype "passive"))
      (node (ref "R8") (pin "2") (pinfunction "2_2") (pintype "passive"))
      (node (ref "U1") (pin "8") (pinfunction "PDI-CLK/~{RESET}_8") (pintype "input"))
    )
    (net (code "49") (name "PDI_DATA") (class "Default")
      (node (ref "J2") (pin "2") (pinfunction "2_2") (pintype "passive"))
      (node (ref "U1") (pin "7") (pinfunction "PDI-DATA_7") (pintype "bidirectional"))
    )
    (net (code "50") (name "PE") (class "Default")
      (node (ref "C23") (pin "2") (pinfunction "2_2") (pintype "passive"))
      (node (ref "C25") (pin "2") (pinfunction "2_2") (pintype "passive"))
      (node (ref "PAD11") (pin "1") (pinfunction "1_1") (pintype "bidirectional"))
      (node (ref "PAD9") (pin "1") (pinfunction "1_1") (pintype "bidirectional"))
    )
    (net (code "51") (name "PWM_LOGIC_0") (class "Default")
      (node (ref "U1") (pin "23") (pinfunction "PD5_23") (pintype "bidirectional"))
    )
    (net (code "52") (name "PWM_LOGIC_1") (class "Default")
      (node (ref "U1") (pin "24") (pinfunction "PD4_24") (pintype "bidirectional"))
    )
    (net (code "53") (name "RESERVED2") (class "Default")
      (node (ref "U1") (pin "13") (pinfunction "PC3_13") (pintype "bidirectional"))
    )
    (net (code "54") (name "RESERVERD") (class "Default")
      (node (ref "U1") (pin "15") (pinfunction "PC1_15") (pintype "bidirectional"))
    )
    (net (code "55") (name "TX_LED_3,3V") (class "Default")
      (node (ref "U1") (pin "16") (pinfunction "PC0_16") (pintype "bidirectional"))
      (node (ref "U2") (pin "2") (pinfunction "A_2") (pintype "bidirectional"))
    )
    (net (code "56") (name "U_VIN") (class "Default")
      (node (ref "C17") (pin "2") (pinfunction "2_2") (pintype "passive"))
      (node (ref "R30") (pin "2") (pinfunction "2_2") (pintype "passive"))
      (node (ref "U1") (pin "4") (pinfunction "PA2_4") (pintype "bidirectional"))
    )
    (net (code "57") (name "VCC") (class "Default")
      (node (ref "C27") (pin "2") (pinfunction "2_2") (pintype "passive"))
      (node (ref "D7") (pin "K") (pinfunction "K_K") (pintype "passive"))
      (node (ref "F1") (pin "1") (pinfunction "1_1") (pintype "passive"))
      (node (ref "IC4") (pin "7") (pinfunction "V+_7") (pintype "power_in"))
      (node (ref "PAD12") (pin "P$1") (pinfunction "1_P$1") (pintype "bidirectional"))
      (node (ref "R19") (pin "1") (pinfunction "1_1") (pintype "passive"))
      (node (ref "R22") (pin "2") (pinfunction "2_2") (pintype "passive"))
    )
    (net (code "58") (name "V_LED") (class "Default")
      (node (ref "IC4") (pin "8") (pinfunction "+IN_8") (pintype "input"))
      (node (ref "PAD14") (pin "P$1") (pinfunction "1_P$1") (pintype "bidirectional"))
      (node (ref "R22") (pin "1") (pinfunction "1_1") (pintype "passive"))
    )
    (net (code "59") (name "unconnected-(IC2A-EDD_IO-Pad6)") (class "Default")
      (node (ref "IC2") (pin "6") (pinfunction "EDD_IO_6") (pintype "bidirectional"))
    )
    (net (code "60") (name "unconnected-(IC2A-EECS-Pad10)") (class "Default")
      (node (ref "IC2") (pin "10") (pinfunction "EECS_10") (pintype "bidirectional"))
    )
    (net (code "61") (name "unconnected-(IC2A-EESK-Pad7)") (class "Default")
      (node (ref "IC2") (pin "7") (pinfunction "EESK_7") (pintype "bidirectional"))
    )
    (net (code "62") (name "unconnected-(IC2A-LED0-Pad1)") (class "Default")
      (node (ref "IC2") (pin "1") (pinfunction "LED0_1") (pintype "bidirectional"))
    )
    (net (code "63") (name "unconnected-(IC2A-LED1-Pad32)") (class "Default")
      (node (ref "IC2") (pin "32") (pinfunction "LED1_32") (pintype "bidirectional"))
    )
    (net (code "64") (name "unconnected-(J2-Pad1)") (class "Default")
      (node (ref "J2") (pin "1") (pinfunction "1_1") (pintype "passive"))
    )
    (net (code "65") (name "unconnected-(J2-Pad3)") (class "Default")
      (node (ref "J2") (pin "3") (pinfunction "3_3") (pintype "passive"))
    )
    (net (code "66") (name "unconnected-(T2-P$4-Pad4)") (class "Default")
      (node (ref "T2") (pin "4") (pinfunction "P$4_4") (pintype "bidirectional"))
    )
    (net (code "67") (name "unconnected-(T2-P$5-Pad5)") (class "Default")
      (node (ref "T2") (pin "5") (pinfunction "P$5_5") (pintype "bidirectional"))
    )
    (net (code "68") (name "unconnected-(T2-P$12-Pad12)") (class "Default")
      (node (ref "T2") (pin "12") (pinfunction "P$12_12") (pintype "bidirectional"))
    )
    (net (code "69") (name "unconnected-(T2-P$13-Pad13)") (class "Default")
      (node (ref "T2") (pin "13") (pinfunction "P$13_13") (pintype "bidirectional"))
    )
    (net (code "70") (name "unconnected-(U1-PA4-Pad2)") (class "Default")
      (node (ref "U1") (pin "2") (pinfunction "PA4_2") (pintype "bidirectional"))
    )
    (net (code "71") (name "unconnected-(U1-PA5-Pad31)") (class "Default")
      (node (ref "U1") (pin "31") (pinfunction "PA5_31") (pintype "bidirectional"))
    )
    (net (code "72") (name "unconnected-(U1-PA6-Pad30)") (class "Default")
      (node (ref "U1") (pin "30") (pinfunction "PA6_30") (pintype "bidirectional"))
    )
    (net (code "73") (name "unconnected-(U1-PA7-Pad29)") (class "Default")
      (node (ref "U1") (pin "29") (pinfunction "PA7_29") (pintype "bidirectional"))
    )
    (net (code "74") (name "unconnected-(U1-PC2-Pad14)") (class "Default")
      (node (ref "U1") (pin "14") (pinfunction "PC2_14") (pintype "bidirectional"))
    )
    (net (code "75") (name "unconnected-(U1-PD0-Pad28)") (class "Default")
      (node (ref "U1") (pin "28") (pinfunction "PD0_28") (pintype "bidirectional"))
    )
    (net (code "76") (name "unconnected-(U1-PD1-Pad27)") (class "Default")
      (node (ref "U1") (pin "27") (pinfunction "PD1_27") (pintype "bidirectional"))
    )
    (net (code "77") (name "unconnected-(U1-PD2-Pad26)") (class "Default")
      (node (ref "U1") (pin "26") (pinfunction "PD2_26") (pintype "bidirectional"))
    )
    (net (code "78") (name "unconnected-(U1-PD3-Pad25)") (class "Default")
      (node (ref "U1") (pin "25") (pinfunction "PD3_25") (pintype "bidirectional"))
    )
    (net (code "79") (name "unconnected-(U1-PD7-Pad21)") (class "Default")
      (node (ref "U1") (pin "21") (pinfunction "PD7_21") (pintype "bidirectional"))
    )
    (net (code "80") (name "unconnected-(U1-PR0-Pad20)") (class "Default")
      (node (ref "U1") (pin "20") (pinfunction "PR0_20") (pintype "bidirectional"))
    )
    (net (code "81") (name "unconnected-(U1-PR1-Pad19)") (class "Default")
      (node (ref "U1") (pin "19") (pinfunction "PR1_19") (pintype "bidirectional"))
    )
    (net (code "82") (name "unconnected-(U2-NC-Pad1)") (class "Default")
      (node (ref "U2") (pin "1") (pinfunction "NC_1") (pintype "passive"))
    )
  )
)
